# EspLight.net
KiCad netlist of a schematic drawn in EAGLE
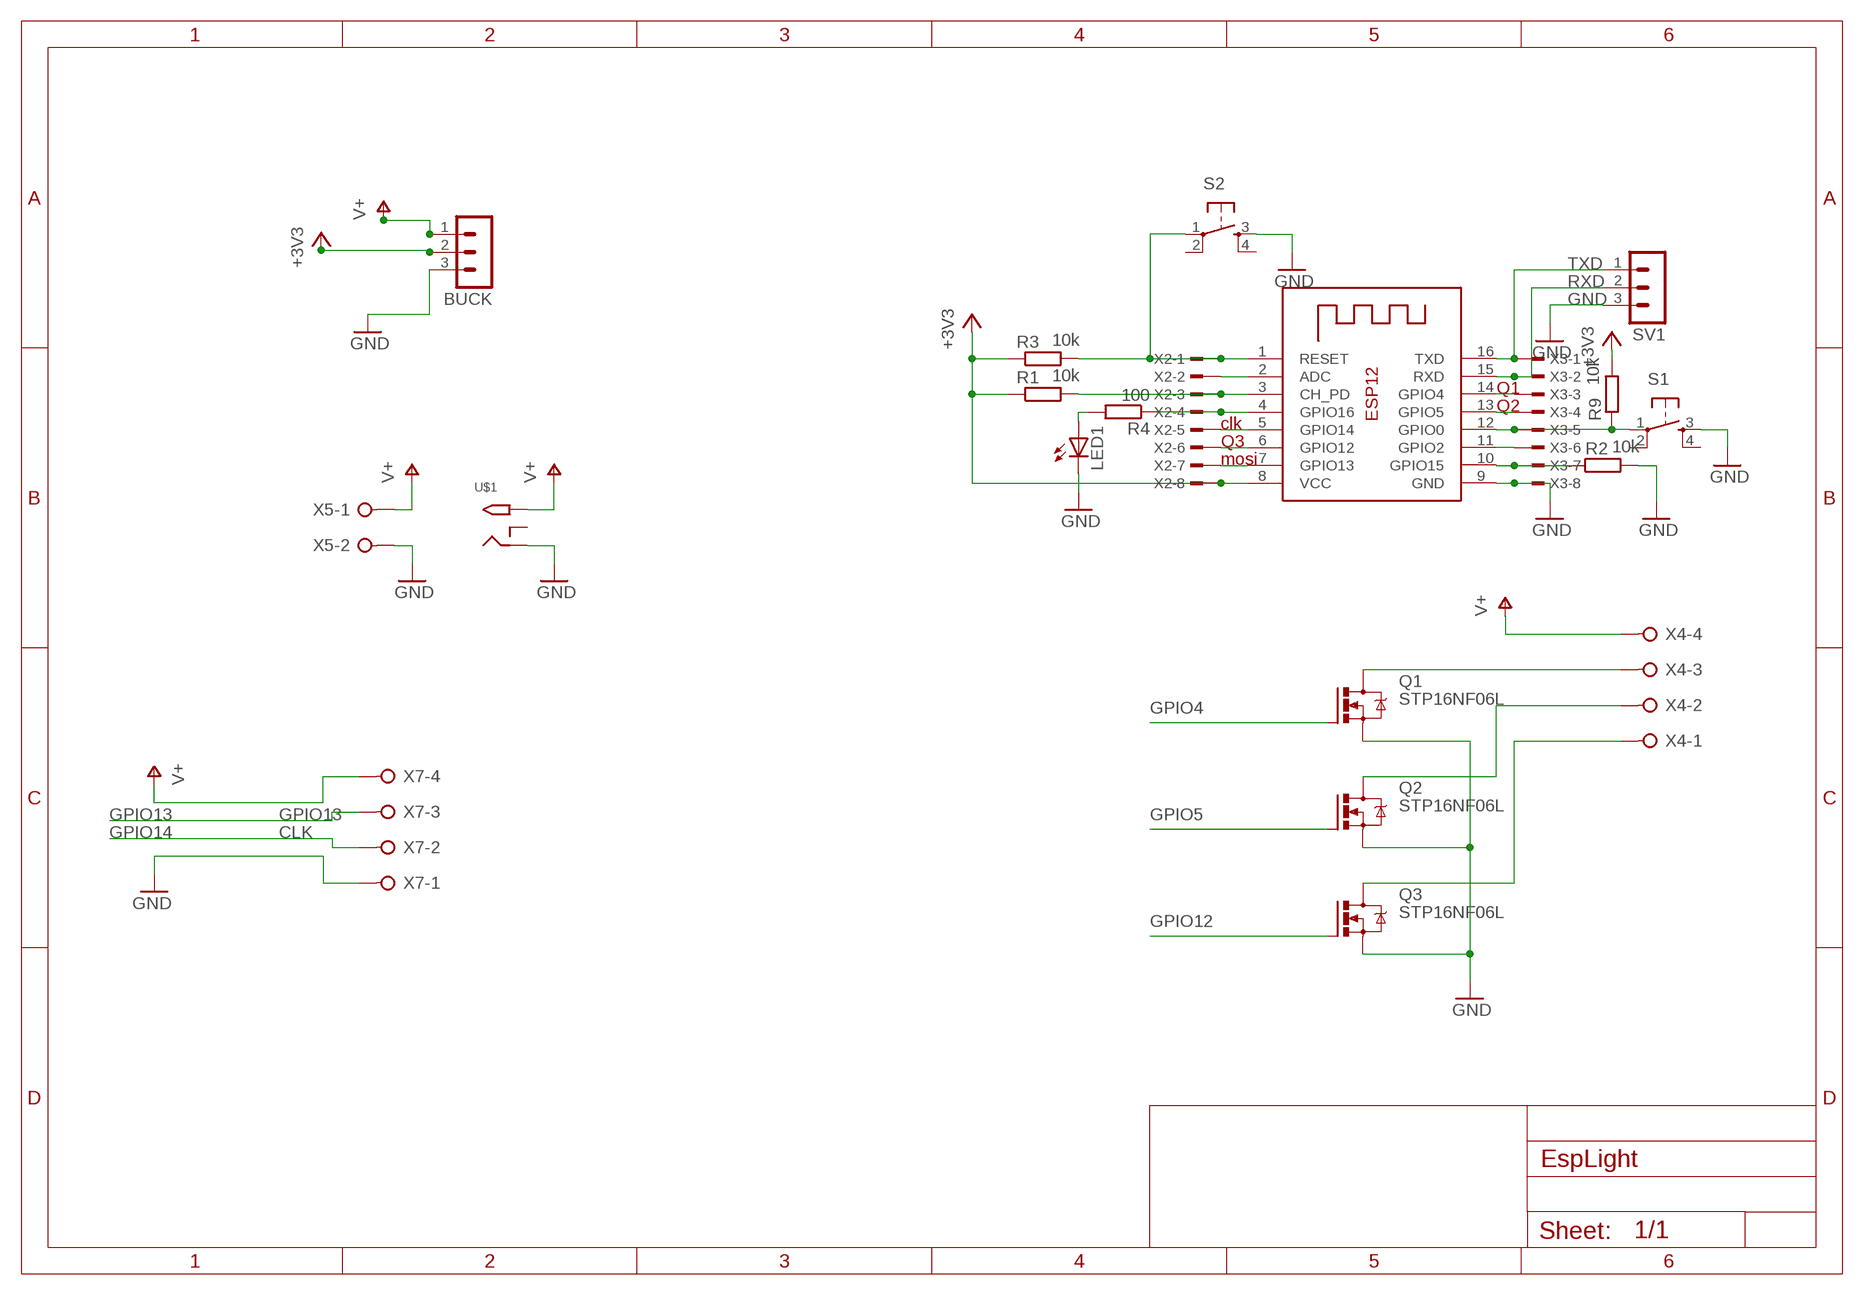
[diagram p0: schematic, sheet 1]

(export (version "E")
  (design (tool "Eeschema 10.0.6"))
  (components
    (comp (ref "BUCK")
      (value "MA03-1")
      (footprint "eagle-import:MA03-1")
      (libsource (lib "eagle-import") (part "MA03-1"))
    )
    (comp (ref "LED1")
      (value "LED5MM")
      (footprint "eagle-import:LED5MM")
      (libsource (lib "eagle-import") (part "LED5MM"))
    )
    (comp (ref "Q1")
      (value "STP16NF06L")
      (footprint "eagle-import:TO220BV")
      (libsource (lib "eagle-import") (part "IRF540"))
    )
    (comp (ref "Q2")
      (value "STP16NF06L")
      (footprint "eagle-import:TO220BV")
      (libsource (lib "eagle-import") (part "IRF540"))
    )
    (comp (ref "Q3")
      (value "STP16NF06L")
      (footprint "eagle-import:TO220BV")
      (libsource (lib "eagle-import") (part "IRF540"))
    )
    (comp (ref "R1")
      (value "10k")
      (footprint "eagle-import:0207_10")
      (libsource (lib "eagle-import") (part "R-EU_0207/10"))
    )
    (comp (ref "R2")
      (value "10k")
      (footprint "eagle-import:0207_10")
      (libsource (lib "eagle-import") (part "R-EU_0207/10"))
    )
    (comp (ref "R3")
      (value "10k")
      (footprint "eagle-import:0207_10")
      (libsource (lib "eagle-import") (part "R-EU_0207/10"))
    )
    (comp (ref "R4")
      (value "100")
      (footprint "eagle-import:0207_10")
      (libsource (lib "eagle-import") (part "R-EU_0207/10"))
    )
    (comp (ref "R9")
      (value "10k")
      (footprint "eagle-import:0207_10")
      (libsource (lib "eagle-import") (part "R-EU_0207/10"))
    )
    (comp (ref "S1")
      (value "TAC_SWITCHPTH")
      (footprint "eagle-import:TACTILE-PTH")
      (libsource (lib "eagle-import") (part "TAC_SWITCHPTH"))
    )
    (comp (ref "S2")
      (value "TAC_SWITCHPTH")
      (footprint "eagle-import:TACTILE-PTH")
      (libsource (lib "eagle-import") (part "TAC_SWITCHPTH"))
    )
    (comp (ref "SV1")
      (value "MA03-1")
      (footprint "eagle-import:MA03-1")
      (libsource (lib "eagle-import") (part "MA03-1"))
    )
    (comp (ref "U$1")
      (value "2.1MMJACKTHM")
      (footprint "eagle-import:PJ-102A")
      (libsource (lib "eagle-import") (part "2.1MMJACKTHM"))
    )
    (comp (ref "X1")
      (value "ESP-12")
      (footprint "eagle-import:ESP-12")
      (libsource (lib "eagle-import") (part "ESP-12"))
    )
    (comp (ref "X2")
      (value "TSW-108-02-S-S")
      (footprint "eagle-import:TSW-108-02-S-S")
      (libsource (lib "eagle-import") (part "TSW-108-02-S-S"))
    )
    (comp (ref "X3")
      (value "TSW-108-02-S-S")
      (footprint "eagle-import:TSW-108-02-S-S")
      (libsource (lib "eagle-import") (part "TSW-108-02-S-S"))
    )
    (comp (ref "X4")
      (value "W237-04P")
      (footprint "eagle-import:W237-4P")
      (libsource (lib "eagle-import") (part "W237-04P"))
    )
    (comp (ref "X5")
      (value "W237-02P")
      (footprint "eagle-import:W237-132")
      (libsource (lib "eagle-import") (part "W237-02P"))
    )
    (comp (ref "X7")
      (value "W237-04P")
      (footprint "eagle-import:W237-4P")
      (libsource (lib "eagle-import") (part "W237-04P"))
    )
  )
  (nets
    (net (code "1") (name "+3V3") (class "Default")
      (node (ref "BUCK") (pin "2") (pinfunction "2_2") (pintype "passive"))
      (node (ref "R1") (pin "1") (pinfunction "1_1") (pintype "passive"))
      (node (ref "R3") (pin "1") (pinfunction "1_1") (pintype "passive"))
      (node (ref "R9") (pin "2") (pinfunction "2_2") (pintype "passive"))
      (node (ref "X1") (pin "8") (pinfunction "VCC_8") (pintype "power_in"))
      (node (ref "X2") (pin "8") (pinfunction "1_8") (pintype "passive"))
    )
    (net (code "2") (name "/GPIO4") (class "Default")
      (node (ref "Q1") (pin "G") (pinfunction "G_G") (pintype "passive"))
      (node (ref "X1") (pin "14") (pinfunction "GPIO4_14") (pintype "bidirectional"))
      (node (ref "X3") (pin "3") (pinfunction "1_3") (pintype "passive"))
    )
    (net (code "3") (name "/GPIO5") (class "Default")
      (node (ref "Q2") (pin "G") (pinfunction "G_G") (pintype "passive"))
      (node (ref "X1") (pin "13") (pinfunction "GPIO5_13") (pintype "bidirectional"))
      (node (ref "X3") (pin "4") (pinfunction "1_4") (pintype "passive"))
    )
    (net (code "4") (name "/GPIO12") (class "Default")
      (node (ref "Q3") (pin "G") (pinfunction "G_G") (pintype "passive"))
      (node (ref "X1") (pin "6") (pinfunction "GPIO12_6") (pintype "bidirectional"))
      (node (ref "X2") (pin "6") (pinfunction "1_6") (pintype "passive"))
    )
    (net (code "5") (name "/GPIO13") (class "Default")
      (node (ref "X1") (pin "7") (pinfunction "GPIO13_7") (pintype "bidirectional"))
      (node (ref "X2") (pin "7") (pinfunction "1_7") (pintype "passive"))
      (node (ref "X7") (pin "3") (pinfunction "KL_3") (pintype "passive"))
    )
    (net (code "6") (name "/GPIO14") (class "Default")
      (node (ref "X1") (pin "5") (pinfunction "GPIO14_5") (pintype "bidirectional"))
      (node (ref "X2") (pin "5") (pinfunction "1_5") (pintype "passive"))
      (node (ref "X7") (pin "2") (pinfunction "KL_2") (pintype "passive"))
    )
    (net (code "7") (name "/RXD") (class "Default")
      (node (ref "SV1") (pin "2") (pinfunction "2_2") (pintype "passive"))
      (node (ref "X1") (pin "15") (pinfunction "RXD_15") (pintype "input"))
      (node (ref "X3") (pin "2") (pinfunction "1_2") (pintype "passive"))
    )
    (net (code "8") (name "/TXD") (class "Default")
      (node (ref "SV1") (pin "1") (pinfunction "1_1") (pintype "passive"))
      (node (ref "X1") (pin "16") (pinfunction "TXD_16") (pintype "output"))
      (node (ref "X3") (pin "1") (pinfunction "1_1") (pintype "passive"))
    )
    (net (code "9") (name "GND") (class "Default")
      (node (ref "BUCK") (pin "3") (pinfunction "3_3") (pintype "passive"))
      (node (ref "LED1") (pin "K") (pinfunction "C_K") (pintype "passive"))
      (node (ref "Q1") (pin "S") (pinfunction "S_S") (pintype "passive"))
      (node (ref "Q2") (pin "S") (pinfunction "S_S") (pintype "passive"))
      (node (ref "Q3") (pin "S") (pinfunction "S_S") (pintype "passive"))
      (node (ref "R2") (pin "2") (pinfunction "2_2") (pintype "passive"))
      (node (ref "S1") (pin "3") (pinfunction "3_3") (pintype "passive"))
      (node (ref "S2") (pin "3") (pinfunction "3_3") (pintype "passive"))
      (node (ref "SV1") (pin "3") (pinfunction "3_3") (pintype "passive"))
      (node (ref "U$1") (pin "RING") (pinfunction "RING_RING") (pintype "bidirectional"))
      (node (ref "X1") (pin "9") (pinfunction "GND_9") (pintype "power_in"))
      (node (ref "X3") (pin "8") (pinfunction "1_8") (pintype "passive"))
      (node (ref "X5") (pin "2") (pinfunction "KL_2") (pintype "passive"))
      (node (ref "X7") (pin "1") (pinfunction "KL_1") (pintype "passive"))
    )
    (net (code "10") (name "Net-(LED1-PadA)") (class "Default")
      (node (ref "LED1") (pin "A") (pinfunction "A_A") (pintype "passive"))
      (node (ref "R4") (pin "2") (pinfunction "2_2") (pintype "passive"))
    )
    (net (code "11") (name "Net-(X1-ADC)") (class "Default")
      (node (ref "X1") (pin "2") (pinfunction "ADC_2") (pintype "passive"))
      (node (ref "X2") (pin "2") (pinfunction "1_2") (pintype "passive"))
    )
    (net (code "12") (name "Net-(X1-CH_PD)") (class "Default")
      (node (ref "R1") (pin "2") (pinfunction "2_2") (pintype "passive"))
      (node (ref "X1") (pin "3") (pinfunction "CH_PD_3") (pintype "input"))
      (node (ref "X2") (pin "3") (pinfunction "1_3") (pintype "passive"))
    )
    (net (code "13") (name "Net-(X1-GPIO0)") (class "Default")
      (node (ref "R9") (pin "1") (pinfunction "1_1") (pintype "passive"))
      (node (ref "S1") (pin "1") (pinfunction "1_1") (pintype "passive"))
      (node (ref "X1") (pin "12") (pinfunction "GPIO0_12") (pintype "bidirectional"))
      (node (ref "X3") (pin "5") (pinfunction "1_5") (pintype "passive"))
    )
    (net (code "14") (name "Net-(X1-GPIO2)") (class "Default")
      (node (ref "X1") (pin "11") (pinfunction "GPIO2_11") (pintype "bidirectional"))
      (node (ref "X3") (pin "6") (pinfunction "1_6") (pintype "passive"))
    )
    (net (code "15") (name "Net-(X1-GPIO15)") (class "Default")
      (node (ref "R2") (pin "1") (pinfunction "1_1") (pintype "passive"))
      (node (ref "X1") (pin "10") (pinfunction "GPIO15_10") (pintype "bidirectional"))
      (node (ref "X3") (pin "7") (pinfunction "1_7") (pintype "passive"))
    )
    (net (code "16") (name "Net-(X1-GPIO16)") (class "Default")
      (node (ref "R4") (pin "1") (pinfunction "1_1") (pintype "passive"))
      (node (ref "X1") (pin "4") (pinfunction "GPIO16_4") (pintype "bidirectional"))
      (node (ref "X2") (pin "4") (pinfunction "1_4") (pintype "passive"))
    )
    (net (code "17") (name "Net-(X1-RESET)") (class "Default")
      (node (ref "R3") (pin "2") (pinfunction "2_2") (pintype "passive"))
      (node (ref "S2") (pin "1") (pinfunction "1_1") (pintype "passive"))
      (node (ref "X1") (pin "1") (pinfunction "RESET_1") (pintype "input"))
      (node (ref "X2") (pin "1") (pinfunction "1_1") (pintype "passive"))
    )
    (net (code "18") (name "Net-(X4A-KL)") (class "Default")
      (node (ref "Q3") (pin "D") (pinfunction "D_D") (pintype "passive"))
      (node (ref "X4") (pin "1") (pinfunction "KL_1") (pintype "passive"))
    )
    (net (code "19") (name "Net-(X4B-KL)") (class "Default")
      (node (ref "Q2") (pin "D") (pinfunction "D_D") (pintype "passive"))
      (node (ref "X4") (pin "2") (pinfunction "KL_2") (pintype "passive"))
    )
    (net (code "20") (name "Net-(X4C-KL)") (class "Default")
      (node (ref "Q1") (pin "D") (pinfunction "D_D") (pintype "passive"))
      (node (ref "X4") (pin "3") (pinfunction "KL_3") (pintype "passive"))
    )
    (net (code "21") (name "V+") (class "Default")
      (node (ref "BUCK") (pin "1") (pinfunction "1_1") (pintype "passive"))
      (node (ref "U$1") (pin "TIP") (pinfunction "TIP_TIP") (pintype "bidirectional"))
      (node (ref "X4") (pin "4") (pinfunction "KL_4") (pintype "passive"))
      (node (ref "X5") (pin "1") (pinfunction "KL_1") (pintype "passive"))
      (node (ref "X7") (pin "4") (pinfunction "KL_4") (pintype "passive"))
    )
    (net (code "22") (name "unconnected-(S1-Pad2)") (class "Default")
      (node (ref "S1") (pin "2") (pinfunction "2_2") (pintype "passive"))
    )
    (net (code "23") (name "unconnected-(S1-Pad4)") (class "Default")
      (node (ref "S1") (pin "4") (pinfunction "4_4") (pintype "passive"))
    )
    (net (code "24") (name "unconnected-(S2-Pad2)") (class "Default")
      (node (ref "S2") (pin "2") (pinfunction "2_2") (pintype "passive"))
    )
    (net (code "25") (name "unconnected-(S2-Pad4)") (class "Default")
      (node (ref "S2") (pin "4") (pinfunction "4_4") (pintype "passive"))
    )
    (net (code "26") (name "unconnected-(U$1-PadRING_SW)") (class "Default")
      (node (ref "U$1") (pin "RING_SW") (pinfunction "RING_SW_RING_SW") (pintype "bidirectional"))
    )
  )
)
